# controller_board.net
KiCad netlist of a schematic drawn in EAGLE
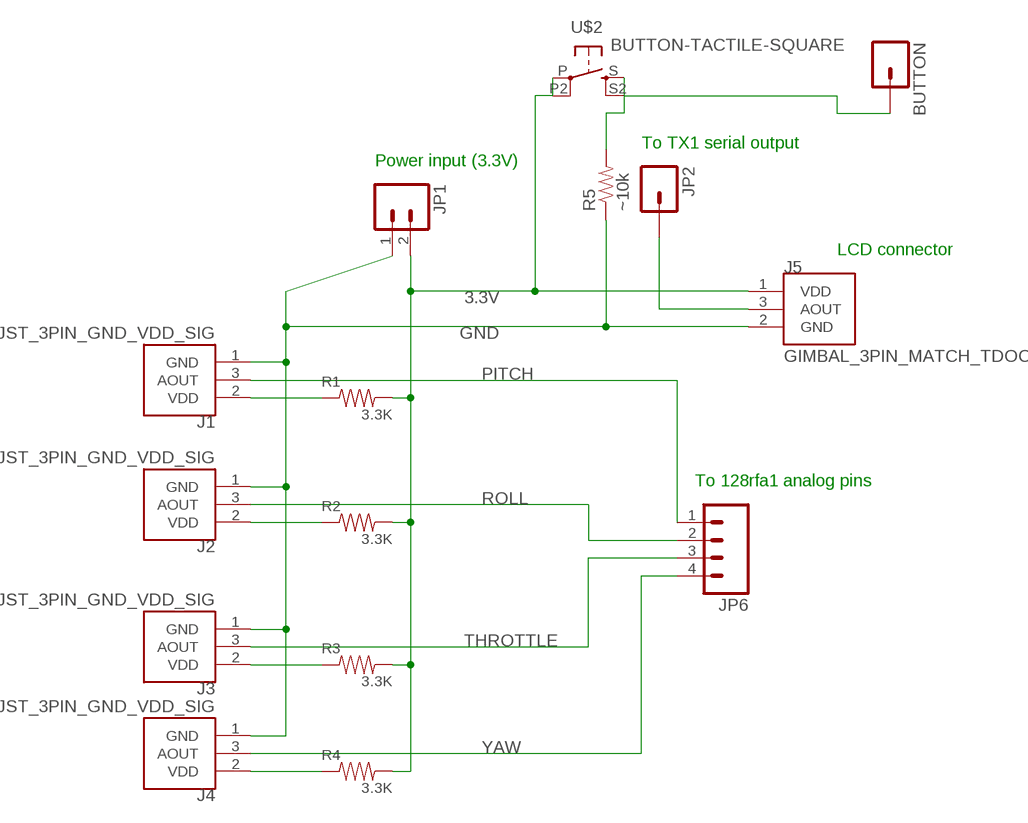
[diagram p0: schematic, sheet 1]

(export (version "E")
  (design (tool "Eeschema 10.0.6"))
  (components
    (comp (ref "BUTTON")
      (value "M01PTH")
      (footprint "eagle-import:1X01")
      (libsource (lib "eagle-import") (part "M01PTH"))
    )
    (comp (ref "J1")
      (value "JST_3PIN_GND_VDD_SIG")
      (footprint "eagle-import:JST-3-PTH-REVERSE")
      (libsource (lib "eagle-import") (part "JST_3PIN_GND_VDD_SIG"))
    )
    (comp (ref "J2")
      (value "JST_3PIN_GND_VDD_SIG")
      (footprint "eagle-import:JST-3-PTH-REVERSE")
      (libsource (lib "eagle-import") (part "JST_3PIN_GND_VDD_SIG"))
    )
    (comp (ref "J3")
      (value "JST_3PIN_GND_VDD_SIG")
      (footprint "eagle-import:JST-3-PTH-REVERSE")
      (libsource (lib "eagle-import") (part "JST_3PIN_GND_VDD_SIG"))
    )
    (comp (ref "J4")
      (value "JST_3PIN_GND_VDD_SIG")
      (footprint "eagle-import:JST-3-PTH-REVERSE")
      (libsource (lib "eagle-import") (part "JST_3PIN_GND_VDD_SIG"))
    )
    (comp (ref "J5")
      (value "GIMBAL_3PIN_MATCH_TDOCU")
      (footprint "eagle-import:JST-3-PTH")
      (libsource (lib "eagle-import") (part "GIMBAL_3PIN_MATCH_TDOCU"))
    )
    (comp (ref "JP1")
      (value "M021X02_NO_SILK")
      (footprint "eagle-import:1X02_NO_SILK")
      (libsource (lib "eagle-import") (part "M021X02_NO_SILK"))
    )
    (comp (ref "JP2")
      (value "M01PTH")
      (footprint "eagle-import:1X01")
      (libsource (lib "eagle-import") (part "M01PTH"))
    )
    (comp (ref "JP6")
      (value "M04PTH")
      (footprint "eagle-import:1X04")
      (libsource (lib "eagle-import") (part "M04PTH"))
    )
    (comp (ref "R1")
      (value "3.3K")
      (footprint "eagle-import:CFR-12")
      (fields (field (name "CREATOR") "Trevor Smith"))
      (libsource (lib "eagle-import") (part "RESISTOR-CFR12"))
    )
    (comp (ref "R2")
      (value "3.3K")
      (footprint "eagle-import:CFR-12")
      (fields (field (name "CREATOR") "Trevor Smith"))
      (libsource (lib "eagle-import") (part "RESISTOR-CFR12"))
    )
    (comp (ref "R3")
      (value "3.3K")
      (footprint "eagle-import:CFR-12")
      (fields (field (name "CREATOR") "Trevor Smith"))
      (libsource (lib "eagle-import") (part "RESISTOR-CFR12"))
    )
    (comp (ref "R4")
      (value "3.3K")
      (footprint "eagle-import:CFR-12")
      (fields (field (name "CREATOR") "Trevor Smith"))
      (libsource (lib "eagle-import") (part "RESISTOR-CFR12"))
    )
    (comp (ref "R5")
      (value "~10k")
      (footprint "eagle-import:AXIAL-0.4")
      (libsource (lib "eagle-import") (part "RESISTORPTH-1/4W"))
    )
    (comp (ref "U$2")
      (value "BUTTON-TACTILE-SQUARE")
      (footprint "eagle-import:BUTTON-TACTILE-SQUARE-ADAFRUIT1010")
      (libsource (lib "eagle-import") (part "BUTTON-TACTILE-SQUARE"))
    )
  )
  (nets
    (net (code "1") (name "/3.3V") (class "Default")
      (node (ref "J5") (pin "1") (pinfunction "VDD_1") (pintype "power_in"))
      (node (ref "JP1") (pin "2") (pinfunction "2_2") (pintype "passive"))
      (node (ref "R1") (pin "P$2") (pinfunction "P$2_P$2") (pintype "passive"))
      (node (ref "R2") (pin "P$2") (pinfunction "P$2_P$2") (pintype "passive"))
      (node (ref "R3") (pin "P$2") (pinfunction "P$2_P$2") (pintype "passive"))
      (node (ref "R4") (pin "P$2") (pinfunction "P$2_P$2") (pintype "passive"))
      (node (ref "U$2") (pin "P") (pinfunction "P_P") (pintype "passive"))
      (node (ref "U$2") (pin "P2") (pinfunction "P1_P2") (pintype "passive"))
    )
    (net (code "2") (name "/GND") (class "Default")
      (node (ref "J1") (pin "1") (pinfunction "GND_1") (pintype "power_in"))
      (node (ref "J2") (pin "1") (pinfunction "GND_1") (pintype "power_in"))
      (node (ref "J3") (pin "1") (pinfunction "GND_1") (pintype "power_in"))
      (node (ref "J4") (pin "1") (pinfunction "GND_1") (pintype "power_in"))
      (node (ref "J5") (pin "2") (pinfunction "GND_2") (pintype "power_in"))
      (node (ref "JP1") (pin "1") (pinfunction "1_1") (pintype "passive"))
      (node (ref "R5") (pin "P$1") (pinfunction "1_P$1") (pintype "passive"))
    )
    (net (code "3") (name "/PITCH") (class "Default")
      (node (ref "J1") (pin "3") (pinfunction "AOUT_3") (pintype "bidirectional"))
      (node (ref "JP6") (pin "1") (pinfunction "1_1") (pintype "passive"))
    )
    (net (code "4") (name "/ROLL") (class "Default")
      (node (ref "J2") (pin "3") (pinfunction "AOUT_3") (pintype "bidirectional"))
      (node (ref "JP6") (pin "2") (pinfunction "2_2") (pintype "passive"))
    )
    (net (code "5") (name "/THROTTLE") (class "Default")
      (node (ref "J3") (pin "3") (pinfunction "AOUT_3") (pintype "bidirectional"))
      (node (ref "JP6") (pin "3") (pinfunction "3_3") (pintype "passive"))
    )
    (net (code "6") (name "/YAW") (class "Default")
      (node (ref "J4") (pin "3") (pinfunction "AOUT_3") (pintype "bidirectional"))
      (node (ref "JP6") (pin "4") (pinfunction "4_4") (pintype "passive"))
    )
    (net (code "7") (name "Net-(J1-VDD)") (class "Default")
      (node (ref "J1") (pin "2") (pinfunction "VDD_2") (pintype "power_in"))
      (node (ref "R1") (pin "P$1") (pinfunction "P$1_P$1") (pintype "passive"))
    )
    (net (code "8") (name "Net-(J2-VDD)") (class "Default")
      (node (ref "J2") (pin "2") (pinfunction "VDD_2") (pintype "power_in"))
      (node (ref "R2") (pin "P$1") (pinfunction "P$1_P$1") (pintype "passive"))
    )
    (net (code "9") (name "Net-(J3-VDD)") (class "Default")
      (node (ref "J3") (pin "2") (pinfunction "VDD_2") (pintype "power_in"))
      (node (ref "R3") (pin "P$1") (pinfunction "P$1_P$1") (pintype "passive"))
    )
    (net (code "10") (name "Net-(J4-VDD)") (class "Default")
      (node (ref "J4") (pin "2") (pinfunction "VDD_2") (pintype "power_in"))
      (node (ref "R4") (pin "P$1") (pinfunction "P$1_P$1") (pintype "passive"))
    )
    (net (code "11") (name "Net-(J5-AOUT)") (class "Default")
      (node (ref "J5") (pin "3") (pinfunction "AOUT_3") (pintype "bidirectional"))
      (node (ref "JP2") (pin "1") (pinfunction "1_1") (pintype "passive"))
    )
    (net (code "12") (name "Net-(R5-2)") (class "Default")
      (node (ref "BUTTON") (pin "1") (pinfunction "1_1") (pintype "passive"))
      (node (ref "R5") (pin "P$2") (pinfunction "2_P$2") (pintype "passive"))
      (node (ref "U$2") (pin "S") (pinfunction "S_S") (pintype "passive"))
      (node (ref "U$2") (pin "S2") (pinfunction "S1_S2") (pintype "passive"))
    )
  )
)
